# LD_driver.net
KiCad netlist of a schematic drawn in Altium Designer
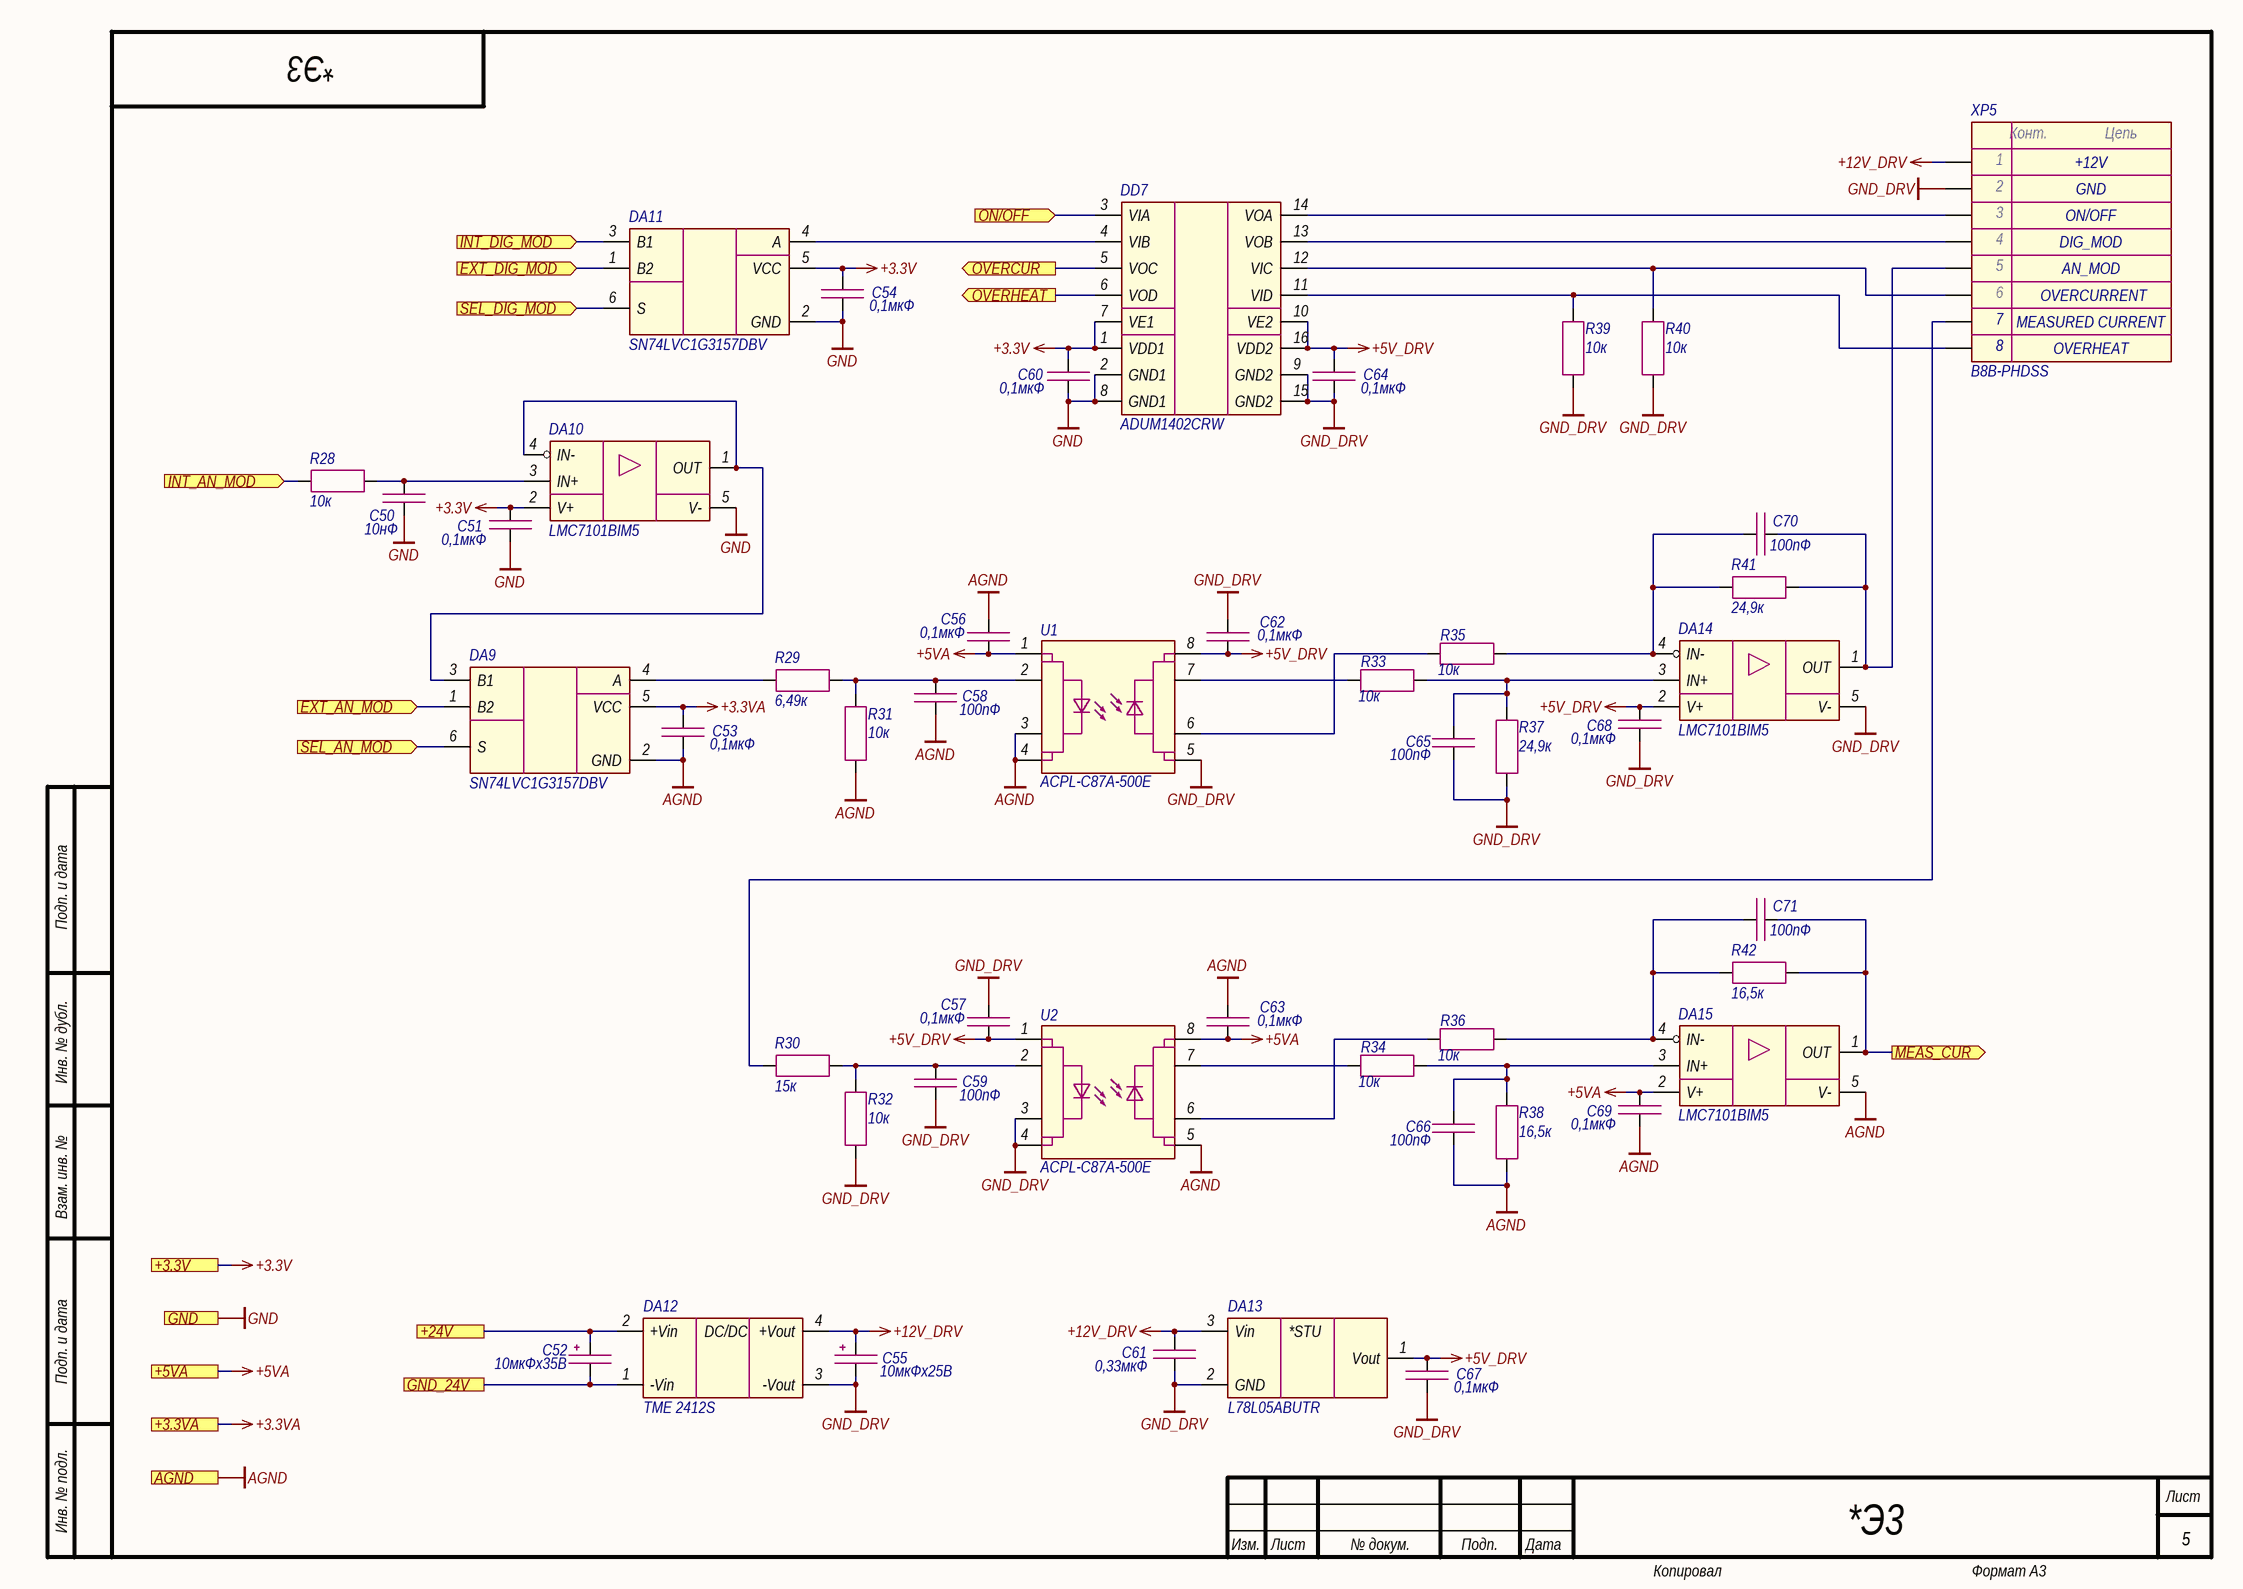
[diagram p0: LD_driver.SchDoc]

(export (version "E")
  (design (tool "Eeschema 10.0.6"))
  (components
    (comp (ref "C50")
      (value "10нФ")
      (footprint "Pcb_library:CAP_0603")
      (fields (field (name "MANUFACTURER") "Murata"))
      (libsource (lib "Schem_library") (part "Capacitor"))
    )
    (comp (ref "C51")
      (value "0,1мкФ")
      (footprint "Pcb_library:CAP_0603")
      (fields (field (name "MANUFACTURER") "Murata"))
      (libsource (lib "Schem_library") (part "Capacitor"))
    )
    (comp (ref "C52")
      (value "10мкФх35B")
      (footprint "Pcb_library:CAP_C")
      (libsource (lib "Schem_library") (part "Capacitor_Polar"))
    )
    (comp (ref "C53")
      (value "0,1мкФ")
      (footprint "Pcb_library:CAP_0603")
      (fields (field (name "MANUFACTURER") "Murata"))
      (libsource (lib "Schem_library") (part "Capacitor"))
    )
    (comp (ref "C54")
      (value "0,1мкФ")
      (footprint "Pcb_library:CAP_0603")
      (fields (field (name "MANUFACTURER") "Murata"))
      (libsource (lib "Schem_library") (part "Capacitor"))
    )
    (comp (ref "C55")
      (value "10мкФх25B")
      (footprint "Pcb_library:CAP_C")
      (libsource (lib "Schem_library") (part "Capacitor_Polar"))
    )
    (comp (ref "C56")
      (value "0,1мкФ")
      (footprint "Pcb_library:CAP_0603")
      (fields (field (name "MANUFACTURER") "Murata"))
      (libsource (lib "Schem_library") (part "Capacitor"))
    )
    (comp (ref "C57")
      (value "0,1мкФ")
      (footprint "Pcb_library:CAP_0603")
      (fields (field (name "MANUFACTURER") "Murata"))
      (libsource (lib "Schem_library") (part "Capacitor"))
    )
    (comp (ref "C58")
      (value "100пФ")
      (footprint "Pcb_library:CAP_0603")
      (fields (field (name "MANUFACTURER") "Murata"))
      (libsource (lib "Schem_library") (part "Capacitor"))
    )
    (comp (ref "C59")
      (value "100пФ")
      (footprint "Pcb_library:CAP_0603")
      (fields (field (name "MANUFACTURER") "Murata"))
      (libsource (lib "Schem_library") (part "Capacitor"))
    )
    (comp (ref "C60")
      (value "0,1мкФ")
      (footprint "Pcb_library:CAP_0603")
      (fields (field (name "MANUFACTURER") "Murata"))
      (libsource (lib "Schem_library") (part "Capacitor"))
    )
    (comp (ref "C61")
      (value "0,33мкФ")
      (footprint "Pcb_library:CAP_0805")
      (fields (field (name "MANUFACTURER") "Murata"))
      (libsource (lib "Schem_library") (part "Capacitor"))
    )
    (comp (ref "C62")
      (value "0,1мкФ")
      (footprint "Pcb_library:CAP_0603")
      (fields (field (name "MANUFACTURER") "Murata"))
      (libsource (lib "Schem_library") (part "Capacitor"))
    )
    (comp (ref "C63")
      (value "0,1мкФ")
      (footprint "Pcb_library:CAP_0603")
      (fields (field (name "MANUFACTURER") "Murata"))
      (libsource (lib "Schem_library") (part "Capacitor"))
    )
    (comp (ref "C64")
      (value "0,1мкФ")
      (footprint "Pcb_library:CAP_0603")
      (fields (field (name "MANUFACTURER") "Murata"))
      (libsource (lib "Schem_library") (part "Capacitor"))
    )
    (comp (ref "C65")
      (value "100пФ")
      (footprint "Pcb_library:CAP_0603")
      (fields (field (name "MANUFACTURER") "Murata"))
      (libsource (lib "Schem_library") (part "Capacitor"))
    )
    (comp (ref "C66")
      (value "100пФ")
      (footprint "Pcb_library:CAP_0603")
      (fields (field (name "MANUFACTURER") "Murata"))
      (libsource (lib "Schem_library") (part "Capacitor"))
    )
    (comp (ref "C67")
      (value "0,1мкФ")
      (footprint "Pcb_library:CAP_0603")
      (fields (field (name "MANUFACTURER") "Murata"))
      (libsource (lib "Schem_library") (part "Capacitor"))
    )
    (comp (ref "C68")
      (value "0,1мкФ")
      (footprint "Pcb_library:CAP_0603")
      (fields (field (name "MANUFACTURER") "Murata"))
      (libsource (lib "Schem_library") (part "Capacitor"))
    )
    (comp (ref "C69")
      (value "0,1мкФ")
      (footprint "Pcb_library:CAP_0603")
      (fields (field (name "MANUFACTURER") "Murata"))
      (libsource (lib "Schem_library") (part "Capacitor"))
    )
    (comp (ref "C70")
      (value "100пФ")
      (footprint "Pcb_library:CAP_0603")
      (fields (field (name "MANUFACTURER") "Murata"))
      (libsource (lib "Schem_library") (part "Capacitor"))
    )
    (comp (ref "C71")
      (value "100пФ")
      (footprint "Pcb_library:CAP_0603")
      (fields (field (name "MANUFACTURER") "Murata"))
      (libsource (lib "Schem_library") (part "Capacitor"))
    )
    (comp (ref "DA9")
      (value "SN74LVC1G3157DBV")
      (footprint "Pcb_library:SOT-23-6")
      (fields (field (name "MANUFACTURER") "Texas Instruments"))
      (libsource (lib "Schem_library") (part "SN74LVC1G3157"))
    )
    (comp (ref "DA10")
      (value "LMC7101BIM5")
      (footprint "Pcb_library:SOT-23-5")
      (fields (field (name "MANUFACTURER") "Texas Instruments"))
      (libsource (lib "Schem_library") (part "LMC7101"))
    )
    (comp (ref "DA11")
      (value "SN74LVC1G3157DBV")
      (footprint "Pcb_library:SOT-23-6")
      (fields (field (name "MANUFACTURER") "Texas Instruments"))
      (libsource (lib "Schem_library") (part "SN74LVC1G3157"))
    )
    (comp (ref "DA12")
      (value "TME 2412S")
      (footprint "Pcb_library:TME (SIP-4)")
      (fields (field (name "MANUFACTURER") "Traco Power"))
      (libsource (lib "Schem_library") (part "TME"))
    )
    (comp (ref "DA13")
      (value "L78L05ABUTR")
      (footprint "Pcb_library:SOT-89")
      (fields (field (name "MANUFACTURER") "STMicroelectronics"))
      (libsource (lib "Schem_library") (part "LD2981ABU50TR"))
    )
    (comp (ref "DA14")
      (value "LMC7101BIM5")
      (footprint "Pcb_library:SOT-23-5")
      (fields (field (name "MANUFACTURER") "Texas Instruments"))
      (libsource (lib "Schem_library") (part "LMC7101"))
    )
    (comp (ref "DA15")
      (value "LMC7101BIM5")
      (footprint "Pcb_library:SOT-23-5")
      (fields (field (name "MANUFACTURER") "Texas Instruments"))
      (libsource (lib "Schem_library") (part "LMC7101"))
    )
    (comp (ref "DD7")
      (value "ADUM1402CRW")
      (footprint "Pcb_library:SOIC-16W")
      (fields (field (name "MANUFACTURER") "Analog Devices"))
      (libsource (lib "Schem_library") (part "ADUM1402"))
    )
    (comp (ref "R28")
      (value "10к")
      (footprint "Pcb_library:RES_0603")
      (fields (field (name "MANUFACTURER") "Yageo"))
      (libsource (lib "Schem_library") (part "Resistor"))
    )
    (comp (ref "R29")
      (value "6,49к")
      (footprint "Pcb_library:RES_0603")
      (fields (field (name "MANUFACTURER") "Yageo"))
      (libsource (lib "Schem_library") (part "Resistor"))
    )
    (comp (ref "R30")
      (value "15к")
      (footprint "Pcb_library:RES_0603")
      (fields (field (name "MANUFACTURER") "Yageo"))
      (libsource (lib "Schem_library") (part "Resistor"))
    )
    (comp (ref "R31")
      (value "10к")
      (footprint "Pcb_library:RES_0603")
      (fields (field (name "MANUFACTURER") "Yageo"))
      (libsource (lib "Schem_library") (part "Resistor"))
    )
    (comp (ref "R32")
      (value "10к")
      (footprint "Pcb_library:RES_0603")
      (fields (field (name "MANUFACTURER") "Yageo"))
      (libsource (lib "Schem_library") (part "Resistor"))
    )
    (comp (ref "R33")
      (value "10к")
      (footprint "Pcb_library:RES_0603")
      (fields (field (name "MANUFACTURER") "Yageo"))
      (libsource (lib "Schem_library") (part "Resistor"))
    )
    (comp (ref "R34")
      (value "10к")
      (footprint "Pcb_library:RES_0603")
      (fields (field (name "MANUFACTURER") "Yageo"))
      (libsource (lib "Schem_library") (part "Resistor"))
    )
    (comp (ref "R35")
      (value "10к")
      (footprint "Pcb_library:RES_0603")
      (fields (field (name "MANUFACTURER") "Yageo"))
      (libsource (lib "Schem_library") (part "Resistor"))
    )
    (comp (ref "R36")
      (value "10к")
      (footprint "Pcb_library:RES_0603")
      (fields (field (name "MANUFACTURER") "Yageo"))
      (libsource (lib "Schem_library") (part "Resistor"))
    )
    (comp (ref "R37")
      (value "24,9к")
      (footprint "Pcb_library:RES_0603")
      (fields (field (name "MANUFACTURER") "Yageo"))
      (libsource (lib "Schem_library") (part "Resistor"))
    )
    (comp (ref "R38")
      (value "16,5к")
      (footprint "Pcb_library:RES_0603")
      (fields (field (name "MANUFACTURER") "Yageo"))
      (libsource (lib "Schem_library") (part "Resistor"))
    )
    (comp (ref "R39")
      (value "10к")
      (footprint "Pcb_library:RES_0603")
      (fields (field (name "MANUFACTURER") "Yageo"))
      (libsource (lib "Schem_library") (part "Resistor"))
    )
    (comp (ref "R40")
      (value "10к")
      (footprint "Pcb_library:RES_0603")
      (fields (field (name "MANUFACTURER") "Yageo"))
      (libsource (lib "Schem_library") (part "Resistor"))
    )
    (comp (ref "R41")
      (value "24,9к")
      (footprint "Pcb_library:RES_0603")
      (fields (field (name "MANUFACTURER") "Yageo"))
      (libsource (lib "Schem_library") (part "Resistor"))
    )
    (comp (ref "R42")
      (value "16,5к")
      (footprint "Pcb_library:RES_0603")
      (fields (field (name "MANUFACTURER") "Yageo"))
      (libsource (lib "Schem_library") (part "Resistor"))
    )
    (comp (ref "U1")
      (value "ACPL-C87A-500E")
      (footprint "Pcb_library:SSO-8")
      (fields (field (name "MANUFACTURER") "Broadcom"))
      (libsource (lib "Schem_library") (part "ACPL-C87"))
    )
    (comp (ref "U2")
      (value "ACPL-C87A-500E")
      (footprint "Pcb_library:SSO-8")
      (fields (field (name "MANUFACTURER") "Broadcom"))
      (libsource (lib "Schem_library") (part "ACPL-C87"))
    )
    (comp (ref "XP5")
      (value "B8B-PHDSS")
      (footprint "Pcb_library:B8B-PHDSS")
      (fields (field (name "MANUFACTURER") "JST"))
      (libsource (lib "Schem_library") (part "Connector-8"))
    )
  )
  (nets
    (net (code "1") (name "+3.3V") (class "Default")
      (node (ref "C51") (pin "1") (pinfunction "1_1") (pintype "passive"))
      (node (ref "C54") (pin "1") (pinfunction "1_1") (pintype "passive"))
      (node (ref "C60") (pin "1") (pinfunction "1_1") (pintype "passive"))
      (node (ref "DA10") (pin "2") (pinfunction "V+_2") (pintype "passive"))
      (node (ref "DA11") (pin "5") (pinfunction "VCC_5") (pintype "passive"))
      (node (ref "DD7") (pin "1") (pinfunction "VDD1_1") (pintype "passive"))
      (node (ref "DD7") (pin "7") (pinfunction "VE1_7") (pintype "passive"))
    )
    (net (code "2") (name "+3.3VA") (class "Default")
      (node (ref "C53") (pin "1") (pinfunction "1_1") (pintype "passive"))
      (node (ref "DA9") (pin "5") (pinfunction "VCC_5") (pintype "passive"))
    )
    (net (code "3") (name "+5VA") (class "Default")
      (node (ref "C56") (pin "1") (pinfunction "1_1") (pintype "passive"))
      (node (ref "C63") (pin "1") (pinfunction "1_1") (pintype "passive"))
      (node (ref "C69") (pin "1") (pinfunction "1_1") (pintype "passive"))
      (node (ref "DA15") (pin "2") (pinfunction "V+_2") (pintype "passive"))
      (node (ref "U1") (pin "1") (pinfunction "VDD1_1") (pintype "passive"))
      (node (ref "U2") (pin "8") (pinfunction "VDD2_8") (pintype "passive"))
    )
    (net (code "4") (name "+5V_DRV") (class "Default")
      (node (ref "C57") (pin "1") (pinfunction "1_1") (pintype "passive"))
      (node (ref "C62") (pin "1") (pinfunction "1_1") (pintype "passive"))
      (node (ref "C64") (pin "1") (pinfunction "1_1") (pintype "passive"))
      (node (ref "C67") (pin "1") (pinfunction "1_1") (pintype "passive"))
      (node (ref "C68") (pin "1") (pinfunction "1_1") (pintype "passive"))
      (node (ref "DA13") (pin "1") (pinfunction "Vout_1") (pintype "passive"))
      (node (ref "DA14") (pin "2") (pinfunction "V+_2") (pintype "passive"))
      (node (ref "DD7") (pin "10") (pinfunction "VE2_10") (pintype "passive"))
      (node (ref "DD7") (pin "16") (pinfunction "VDD2_16") (pintype "passive"))
      (node (ref "U1") (pin "8") (pinfunction "VDD2_8") (pintype "passive"))
      (node (ref "U2") (pin "1") (pinfunction "VDD1_1") (pintype "passive"))
    )
    (net (code "5") (name "+12V_DRV") (class "Default")
      (node (ref "C55") (pin "1") (pinfunction "1_1") (pintype "passive"))
      (node (ref "C61") (pin "2") (pinfunction "2_2") (pintype "passive"))
      (node (ref "DA12") (pin "4") (pinfunction "+Vout_4") (pintype "passive"))
      (node (ref "DA13") (pin "3") (pinfunction "Vin_3") (pintype "passive"))
      (node (ref "XP5") (pin "1") (pintype "passive"))
    )
    (net (code "6") (name "/+24V") (class "Default")
      (node (ref "C52") (pin "1") (pinfunction "1_1") (pintype "passive"))
      (node (ref "DA12") (pin "2") (pinfunction "+Vin_2") (pintype "passive"))
    )
    (net (code "7") (name "/EXT_AN_MOD") (class "Default")
      (node (ref "DA9") (pin "1") (pinfunction "B2_1") (pintype "passive"))
    )
    (net (code "8") (name "/EXT_DIG_MOD") (class "Default")
      (node (ref "DA11") (pin "1") (pinfunction "B2_1") (pintype "passive"))
    )
    (net (code "9") (name "/GND_24V") (class "Default")
      (node (ref "C52") (pin "2") (pinfunction "2_2") (pintype "passive"))
      (node (ref "DA12") (pin "1") (pinfunction "-Vin_1") (pintype "passive"))
    )
    (net (code "10") (name "/INT_AN_MOD") (class "Default")
      (node (ref "R28") (pin "1") (pinfunction "1_1") (pintype "passive"))
    )
    (net (code "11") (name "/INT_DIG_MOD") (class "Default")
      (node (ref "DA11") (pin "3") (pinfunction "B1_3") (pintype "passive"))
    )
    (net (code "12") (name "/MEAS_CUR") (class "Default")
      (node (ref "C71") (pin "2") (pinfunction "2_2") (pintype "passive"))
      (node (ref "DA15") (pin "1") (pinfunction "OUT_1") (pintype "passive"))
      (node (ref "R42") (pin "1") (pinfunction "1_1") (pintype "passive"))
    )
    (net (code "13") (name "/ON{slash}OFF") (class "Default")
      (node (ref "DD7") (pin "3") (pinfunction "VIA_3") (pintype "passive"))
    )
    (net (code "14") (name "/OVERCUR") (class "Default")
      (node (ref "DD7") (pin "5") (pinfunction "VOC_5") (pintype "passive"))
    )
    (net (code "15") (name "/OVERHEAT") (class "Default")
      (node (ref "DD7") (pin "6") (pinfunction "VOD_6") (pintype "passive"))
    )
    (net (code "16") (name "/SEL_AN_MOD") (class "Default")
      (node (ref "DA9") (pin "6") (pinfunction "S_6") (pintype "passive"))
    )
    (net (code "17") (name "/SEL_DIG_MOD") (class "Default")
      (node (ref "DA11") (pin "6") (pinfunction "S_6") (pintype "passive"))
    )
    (net (code "18") (name "AGND") (class "Default")
      (node (ref "C53") (pin "2") (pinfunction "2_2") (pintype "passive"))
      (node (ref "C56") (pin "2") (pinfunction "2_2") (pintype "passive"))
      (node (ref "C58") (pin "1") (pinfunction "1_1") (pintype "passive"))
      (node (ref "C63") (pin "2") (pinfunction "2_2") (pintype "passive"))
      (node (ref "C66") (pin "2") (pinfunction "2_2") (pintype "passive"))
      (node (ref "C69") (pin "2") (pinfunction "2_2") (pintype "passive"))
      (node (ref "DA15") (pin "5") (pinfunction "V-_5") (pintype "passive"))
      (node (ref "DA9") (pin "2") (pinfunction "GND_2") (pintype "passive"))
      (node (ref "R31") (pin "2") (pinfunction "2_2") (pintype "passive"))
      (node (ref "R38") (pin "2") (pinfunction "2_2") (pintype "passive"))
      (node (ref "U1") (pin "3") (pinfunction "SHDN_3") (pintype "passive"))
      (node (ref "U1") (pin "4") (pinfunction "GND1_4") (pintype "passive"))
      (node (ref "U2") (pin "5") (pinfunction "GND2_5") (pintype "passive"))
    )
    (net (code "19") (name "GND") (class "Default")
      (node (ref "C50") (pin "2") (pinfunction "2_2") (pintype "passive"))
      (node (ref "C51") (pin "2") (pinfunction "2_2") (pintype "passive"))
      (node (ref "C54") (pin "2") (pinfunction "2_2") (pintype "passive"))
      (node (ref "C60") (pin "2") (pinfunction "2_2") (pintype "passive"))
      (node (ref "DA10") (pin "5") (pinfunction "V-_5") (pintype "passive"))
      (node (ref "DA11") (pin "2") (pinfunction "GND_2") (pintype "passive"))
      (node (ref "DD7") (pin "2") (pinfunction "GND1_2") (pintype "passive"))
      (node (ref "DD7") (pin "8") (pinfunction "GND1_8") (pintype "passive"))
    )
    (net (code "20") (name "GND_DRV") (class "Default")
      (node (ref "C55") (pin "2") (pinfunction "2_2") (pintype "passive"))
      (node (ref "C57") (pin "2") (pinfunction "2_2") (pintype "passive"))
      (node (ref "C59") (pin "1") (pinfunction "1_1") (pintype "passive"))
      (node (ref "C61") (pin "1") (pinfunction "1_1") (pintype "passive"))
      (node (ref "C62") (pin "2") (pinfunction "2_2") (pintype "passive"))
      (node (ref "C64") (pin "2") (pinfunction "2_2") (pintype "passive"))
      (node (ref "C65") (pin "2") (pinfunction "2_2") (pintype "passive"))
      (node (ref "C67") (pin "2") (pinfunction "2_2") (pintype "passive"))
      (node (ref "C68") (pin "2") (pinfunction "2_2") (pintype "passive"))
      (node (ref "DA12") (pin "3") (pinfunction "-Vout_3") (pintype "passive"))
      (node (ref "DA13") (pin "2") (pinfunction "GND_2") (pintype "passive"))
      (node (ref "DA14") (pin "5") (pinfunction "V-_5") (pintype "passive"))
      (node (ref "DD7") (pin "15") (pinfunction "GND2_15") (pintype "passive"))
      (node (ref "DD7") (pin "9") (pinfunction "GND2_9") (pintype "passive"))
      (node (ref "R32") (pin "2") (pinfunction "2_2") (pintype "passive"))
      (node (ref "R37") (pin "1") (pinfunction "1_1") (pintype "passive"))
      (node (ref "R39") (pin "2") (pinfunction "2_2") (pintype "passive"))
      (node (ref "R40") (pin "2") (pinfunction "2_2") (pintype "passive"))
      (node (ref "U1") (pin "5") (pinfunction "GND2_5") (pintype "passive"))
      (node (ref "U2") (pin "3") (pinfunction "SHDN_3") (pintype "passive"))
      (node (ref "U2") (pin "4") (pinfunction "GND1_4") (pintype "passive"))
      (node (ref "XP5") (pin "2") (pintype "passive"))
    )
    (net (code "21") (name "Net-(DA9-A)") (class "Default")
      (node (ref "DA9") (pin "4") (pinfunction "A_4") (pintype "passive"))
      (node (ref "R29") (pin "2") (pinfunction "2_2") (pintype "passive"))
    )
    (net (code "22") (name "Net-(DA10-IN+)") (class "Default")
      (node (ref "C50") (pin "1") (pinfunction "1_1") (pintype "passive"))
      (node (ref "DA10") (pin "3") (pinfunction "IN+_3") (pintype "passive"))
      (node (ref "R28") (pin "2") (pinfunction "2_2") (pintype "passive"))
    )
    (net (code "23") (name "Net-(DA10-IN-)") (class "Default")
      (node (ref "DA10") (pin "1") (pinfunction "OUT_1") (pintype "passive"))
      (node (ref "DA10") (pin "4") (pinfunction "IN-_4") (pintype "passive"))
      (node (ref "DA9") (pin "3") (pinfunction "B1_3") (pintype "passive"))
    )
    (net (code "24") (name "Net-(DA11-A)") (class "Default")
      (node (ref "DA11") (pin "4") (pinfunction "A_4") (pintype "passive"))
      (node (ref "DD7") (pin "4") (pinfunction "VIB_4") (pintype "passive"))
    )
    (net (code "25") (name "Net-(DA14-IN+)") (class "Default")
      (node (ref "C65") (pin "1") (pinfunction "1_1") (pintype "passive"))
      (node (ref "DA14") (pin "3") (pinfunction "IN+_3") (pintype "passive"))
      (node (ref "R33") (pin "2") (pinfunction "2_2") (pintype "passive"))
      (node (ref "R37") (pin "2") (pinfunction "2_2") (pintype "passive"))
    )
    (net (code "26") (name "Net-(DA14-IN-)") (class "Default")
      (node (ref "C70") (pin "1") (pinfunction "1_1") (pintype "passive"))
      (node (ref "DA14") (pin "4") (pinfunction "IN-_4") (pintype "passive"))
      (node (ref "R35") (pin "2") (pinfunction "2_2") (pintype "passive"))
      (node (ref "R41") (pin "1") (pinfunction "1_1") (pintype "passive"))
    )
    (net (code "27") (name "Net-(DA14-OUT)") (class "Default")
      (node (ref "C70") (pin "2") (pinfunction "2_2") (pintype "passive"))
      (node (ref "DA14") (pin "1") (pinfunction "OUT_1") (pintype "passive"))
      (node (ref "R41") (pin "2") (pinfunction "2_2") (pintype "passive"))
      (node (ref "XP5") (pin "5") (pintype "passive"))
    )
    (net (code "28") (name "Net-(DA15-IN+)") (class "Default")
      (node (ref "C66") (pin "1") (pinfunction "1_1") (pintype "passive"))
      (node (ref "DA15") (pin "3") (pinfunction "IN+_3") (pintype "passive"))
      (node (ref "R34") (pin "2") (pinfunction "2_2") (pintype "passive"))
      (node (ref "R38") (pin "1") (pinfunction "1_1") (pintype "passive"))
    )
    (net (code "29") (name "Net-(DA15-IN-)") (class "Default")
      (node (ref "C71") (pin "1") (pinfunction "1_1") (pintype "passive"))
      (node (ref "DA15") (pin "4") (pinfunction "IN-_4") (pintype "passive"))
      (node (ref "R36") (pin "2") (pinfunction "2_2") (pintype "passive"))
      (node (ref "R42") (pin "2") (pinfunction "2_2") (pintype "passive"))
    )
    (net (code "30") (name "Net-(DD7-VIC)") (class "Default")
      (node (ref "DD7") (pin "12") (pinfunction "VIC_12") (pintype "passive"))
      (node (ref "R40") (pin "1") (pinfunction "1_1") (pintype "passive"))
      (node (ref "XP5") (pin "6") (pintype "passive"))
    )
    (net (code "31") (name "Net-(DD7-VID)") (class "Default")
      (node (ref "DD7") (pin "11") (pinfunction "VID_11") (pintype "passive"))
      (node (ref "R39") (pin "1") (pinfunction "1_1") (pintype "passive"))
      (node (ref "XP5") (pin "8") (pintype "passive"))
    )
    (net (code "32") (name "Net-(DD7-VOA)") (class "Default")
      (node (ref "DD7") (pin "14") (pinfunction "VOA_14") (pintype "passive"))
      (node (ref "XP5") (pin "3") (pintype "passive"))
    )
    (net (code "33") (name "Net-(DD7-VOB)") (class "Default")
      (node (ref "DD7") (pin "13") (pinfunction "VOB_13") (pintype "passive"))
      (node (ref "XP5") (pin "4") (pintype "passive"))
    )
    (net (code "34") (name "Net-(R30-Pad2)") (class "Default")
      (node (ref "R30") (pin "2") (pinfunction "2_2") (pintype "passive"))
      (node (ref "XP5") (pin "7") (pintype "passive"))
    )
    (net (code "35") (name "Net-(U1-VIN)") (class "Default")
      (node (ref "C58") (pin "2") (pinfunction "2_2") (pintype "passive"))
      (node (ref "R29") (pin "1") (pinfunction "1_1") (pintype "passive"))
      (node (ref "R31") (pin "1") (pinfunction "1_1") (pintype "passive"))
      (node (ref "U1") (pin "2") (pinfunction "VIN_2") (pintype "passive"))
    )
    (net (code "36") (name "Net-(U1-VOUT+)") (class "Default")
      (node (ref "R33") (pin "1") (pinfunction "1_1") (pintype "passive"))
      (node (ref "U1") (pin "7") (pinfunction "VOUT+_7") (pintype "passive"))
    )
    (net (code "37") (name "Net-(U1-VOUT-)") (class "Default")
      (node (ref "R35") (pin "1") (pinfunction "1_1") (pintype "passive"))
      (node (ref "U1") (pin "6") (pinfunction "VOUT-_6") (pintype "passive"))
    )
    (net (code "38") (name "Net-(U2-VIN)") (class "Default")
      (node (ref "C59") (pin "2") (pinfunction "2_2") (pintype "passive"))
      (node (ref "R30") (pin "1") (pinfunction "1_1") (pintype "passive"))
      (node (ref "R32") (pin "1") (pinfunction "1_1") (pintype "passive"))
      (node (ref "U2") (pin "2") (pinfunction "VIN_2") (pintype "passive"))
    )
    (net (code "39") (name "Net-(U2-VOUT+)") (class "Default")
      (node (ref "R34") (pin "1") (pinfunction "1_1") (pintype "passive"))
      (node (ref "U2") (pin "7") (pinfunction "VOUT+_7") (pintype "passive"))
    )
    (net (code "40") (name "Net-(U2-VOUT-)") (class "Default")
      (node (ref "R36") (pin "1") (pinfunction "1_1") (pintype "passive"))
      (node (ref "U2") (pin "6") (pinfunction "VOUT-_6") (pintype "passive"))
    )
  )
)
